# ADDER_auto.net
KiCad netlist of a schematic drawn in EAGLE
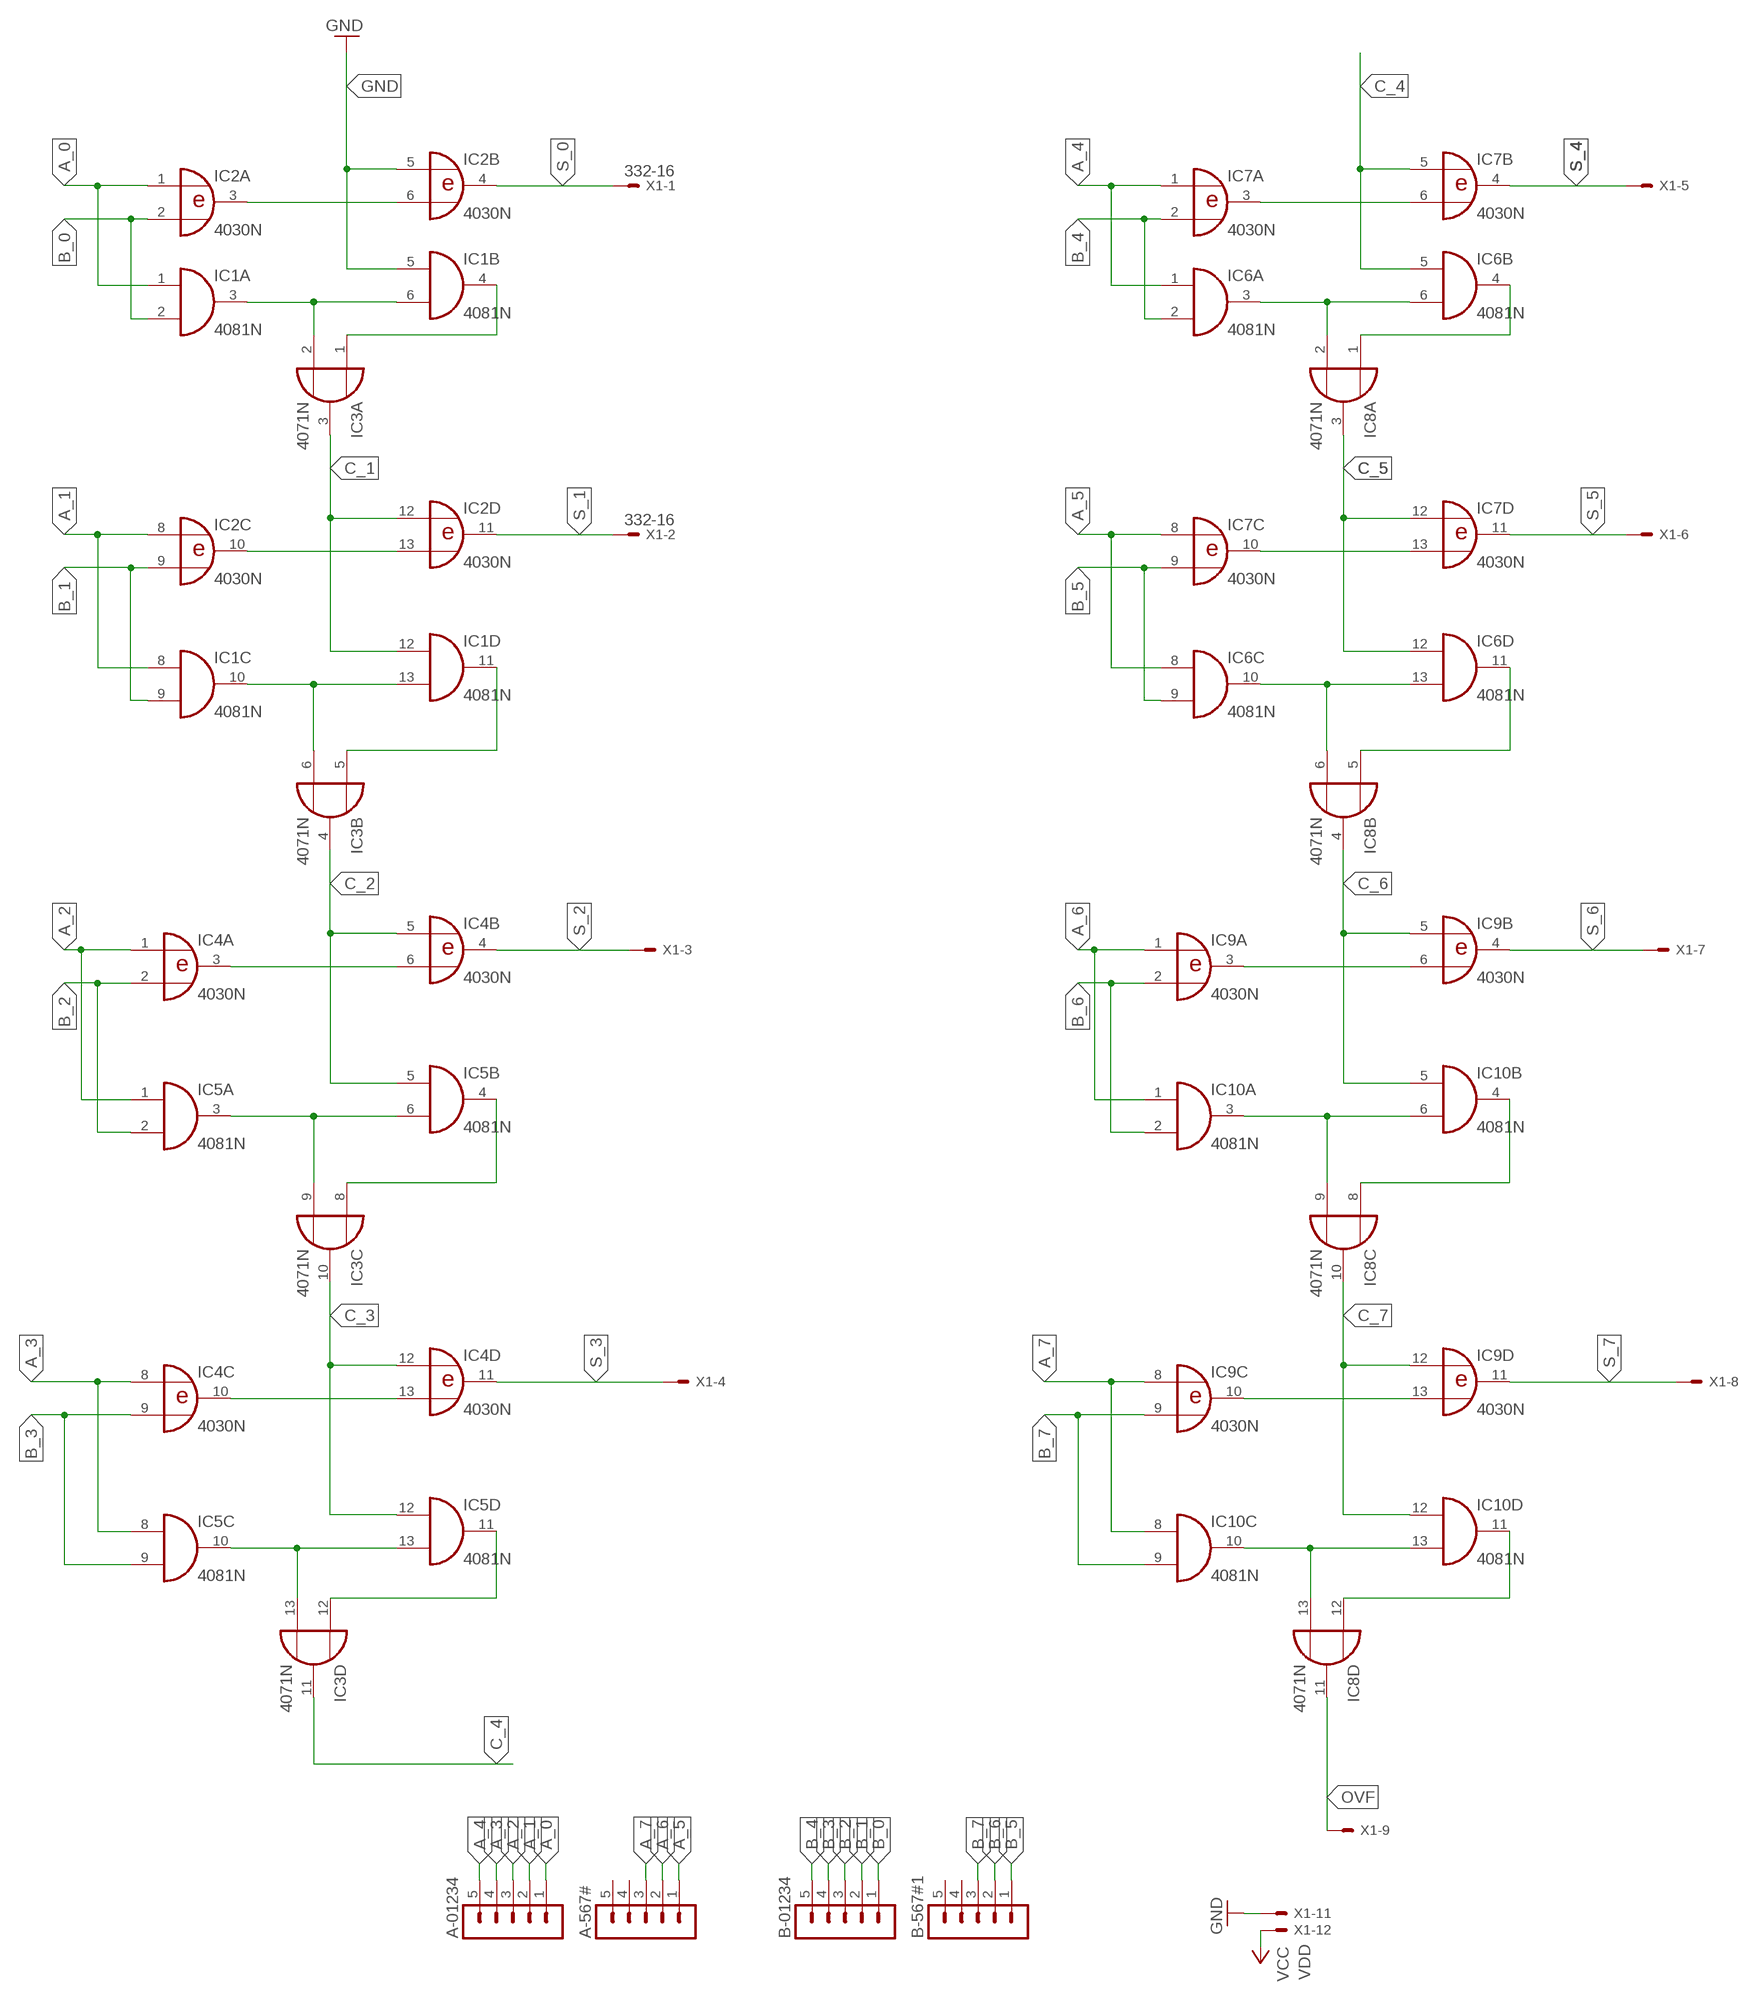
[diagram p0: schematic, sheet 1]

(export (version "E")
  (design (tool "Eeschema 10.0.6"))
  (components
    (comp (ref "A-567#")
      (value "MA05-1")
      (footprint "eagle-import:MA05-1")
      (libsource (lib "eagle-import") (part "MA05-1"))
    )
    (comp (ref "A-01234")
      (value "MA05-1")
      (footprint "eagle-import:MA05-1")
      (libsource (lib "eagle-import") (part "MA05-1"))
    )
    (comp (ref "B-567#1")
      (value "MA05-1")
      (footprint "eagle-import:MA05-1")
      (libsource (lib "eagle-import") (part "MA05-1"))
    )
    (comp (ref "B-01234")
      (value "MA05-1")
      (footprint "eagle-import:MA05-1")
      (libsource (lib "eagle-import") (part "MA05-1"))
    )
    (comp (ref "IC1")
      (value "4081N")
      (footprint "eagle-import:DIL14")
      (libsource (lib "eagle-import") (part "4081N"))
    )
    (comp (ref "IC2")
      (value "4030N")
      (footprint "eagle-import:DIL14")
      (libsource (lib "eagle-import") (part "4030N"))
    )
    (comp (ref "IC3")
      (value "4071N")
      (footprint "eagle-import:DIL14")
      (libsource (lib "eagle-import") (part "4071N"))
    )
    (comp (ref "IC4")
      (value "4030N")
      (footprint "eagle-import:DIL14")
      (libsource (lib "eagle-import") (part "4030N"))
    )
    (comp (ref "IC5")
      (value "4081N")
      (footprint "eagle-import:DIL14")
      (libsource (lib "eagle-import") (part "4081N"))
    )
    (comp (ref "IC6")
      (value "4081N")
      (footprint "eagle-import:DIL14")
      (libsource (lib "eagle-import") (part "4081N"))
    )
    (comp (ref "IC7")
      (value "4030N")
      (footprint "eagle-import:DIL14")
      (libsource (lib "eagle-import") (part "4030N"))
    )
    (comp (ref "IC8")
      (value "4071N")
      (footprint "eagle-import:DIL14")
      (libsource (lib "eagle-import") (part "4071N"))
    )
    (comp (ref "IC9")
      (value "4030N")
      (footprint "eagle-import:DIL14")
      (libsource (lib "eagle-import") (part "4030N"))
    )
    (comp (ref "IC10")
      (value "4081N")
      (footprint "eagle-import:DIL14")
      (libsource (lib "eagle-import") (part "4081N"))
    )
    (comp (ref "X1")
      (value "332-16")
      (footprint "eagle-import:332-16")
      (libsource (lib "eagle-import") (part "332-16"))
    )
  )
  (nets
    (net (code "1") (name "A_0") (class "Default")
      (node (ref "A-01234") (pin "1") (pinfunction "1_1") (pintype "passive"))
      (node (ref "IC1") (pin "1") (pinfunction "I0_1") (pintype "input"))
      (node (ref "IC2") (pin "1") (pinfunction "I0_1") (pintype "input"))
    )
    (net (code "2") (name "A_1") (class "Default")
      (node (ref "A-01234") (pin "2") (pinfunction "2_2") (pintype "passive"))
      (node (ref "IC1") (pin "8") (pinfunction "I0_8") (pintype "input"))
      (node (ref "IC2") (pin "8") (pinfunction "I0_8") (pintype "input"))
    )
    (net (code "3") (name "A_2") (class "Default")
      (node (ref "A-01234") (pin "3") (pinfunction "3_3") (pintype "passive"))
      (node (ref "IC4") (pin "1") (pinfunction "I0_1") (pintype "input"))
      (node (ref "IC5") (pin "1") (pinfunction "I0_1") (pintype "input"))
    )
    (net (code "4") (name "A_3") (class "Default")
      (node (ref "A-01234") (pin "4") (pinfunction "4_4") (pintype "passive"))
      (node (ref "IC4") (pin "8") (pinfunction "I0_8") (pintype "input"))
      (node (ref "IC5") (pin "8") (pinfunction "I0_8") (pintype "input"))
    )
    (net (code "5") (name "A_4") (class "Default")
      (node (ref "A-01234") (pin "5") (pinfunction "5_5") (pintype "passive"))
      (node (ref "IC6") (pin "1") (pinfunction "I0_1") (pintype "input"))
      (node (ref "IC7") (pin "1") (pinfunction "I0_1") (pintype "input"))
    )
    (net (code "6") (name "A_5") (class "Default")
      (node (ref "A-567#") (pin "1") (pinfunction "1_1") (pintype "passive"))
      (node (ref "IC6") (pin "8") (pinfunction "I0_8") (pintype "input"))
      (node (ref "IC7") (pin "8") (pinfunction "I0_8") (pintype "input"))
    )
    (net (code "7") (name "A_6") (class "Default")
      (node (ref "A-567#") (pin "2") (pinfunction "2_2") (pintype "passive"))
      (node (ref "IC10") (pin "1") (pinfunction "I0_1") (pintype "input"))
      (node (ref "IC9") (pin "1") (pinfunction "I0_1") (pintype "input"))
    )
    (net (code "8") (name "A_7") (class "Default")
      (node (ref "A-567#") (pin "3") (pinfunction "3_3") (pintype "passive"))
      (node (ref "IC10") (pin "8") (pinfunction "I0_8") (pintype "input"))
      (node (ref "IC9") (pin "8") (pinfunction "I0_8") (pintype "input"))
    )
    (net (code "9") (name "B_0") (class "Default")
      (node (ref "B-01234") (pin "1") (pinfunction "1_1") (pintype "passive"))
      (node (ref "IC1") (pin "2") (pinfunction "I1_2") (pintype "input"))
      (node (ref "IC2") (pin "2") (pinfunction "I1_2") (pintype "input"))
    )
    (net (code "10") (name "B_1") (class "Default")
      (node (ref "B-01234") (pin "2") (pinfunction "2_2") (pintype "passive"))
      (node (ref "IC1") (pin "9") (pinfunction "I1_9") (pintype "input"))
      (node (ref "IC2") (pin "9") (pinfunction "I1_9") (pintype "input"))
    )
    (net (code "11") (name "B_2") (class "Default")
      (node (ref "B-01234") (pin "3") (pinfunction "3_3") (pintype "passive"))
      (node (ref "IC4") (pin "2") (pinfunction "I1_2") (pintype "input"))
      (node (ref "IC5") (pin "2") (pinfunction "I1_2") (pintype "input"))
    )
    (net (code "12") (name "B_3") (class "Default")
      (node (ref "B-01234") (pin "4") (pinfunction "4_4") (pintype "passive"))
      (node (ref "IC4") (pin "9") (pinfunction "I1_9") (pintype "input"))
      (node (ref "IC5") (pin "9") (pinfunction "I1_9") (pintype "input"))
    )
    (net (code "13") (name "B_4") (class "Default")
      (node (ref "B-01234") (pin "5") (pinfunction "5_5") (pintype "passive"))
      (node (ref "IC6") (pin "2") (pinfunction "I1_2") (pintype "input"))
      (node (ref "IC7") (pin "2") (pinfunction "I1_2") (pintype "input"))
    )
    (net (code "14") (name "B_5") (class "Default")
      (node (ref "B-567#1") (pin "1") (pinfunction "1_1") (pintype "passive"))
      (node (ref "IC6") (pin "9") (pinfunction "I1_9") (pintype "input"))
      (node (ref "IC7") (pin "9") (pinfunction "I1_9") (pintype "input"))
    )
    (net (code "15") (name "B_6") (class "Default")
      (node (ref "B-567#1") (pin "2") (pinfunction "2_2") (pintype "passive"))
      (node (ref "IC10") (pin "2") (pinfunction "I1_2") (pintype "input"))
      (node (ref "IC9") (pin "2") (pinfunction "I1_2") (pintype "input"))
    )
    (net (code "16") (name "B_7") (class "Default")
      (node (ref "B-567#1") (pin "3") (pinfunction "3_3") (pintype "passive"))
      (node (ref "IC10") (pin "9") (pinfunction "I1_9") (pintype "input"))
      (node (ref "IC9") (pin "9") (pinfunction "I1_9") (pintype "input"))
    )
    (net (code "17") (name "C_1") (class "Default")
      (node (ref "IC1") (pin "12") (pinfunction "I0_12") (pintype "input"))
      (node (ref "IC2") (pin "12") (pinfunction "I0_12") (pintype "input"))
      (node (ref "IC3") (pin "3") (pinfunction "O_3") (pintype "output"))
    )
    (net (code "18") (name "C_2") (class "Default")
      (node (ref "IC3") (pin "4") (pinfunction "O_4") (pintype "output"))
      (node (ref "IC4") (pin "5") (pinfunction "I0_5") (pintype "input"))
      (node (ref "IC5") (pin "5") (pinfunction "I0_5") (pintype "input"))
    )
    (net (code "19") (name "C_3") (class "Default")
      (node (ref "IC3") (pin "10") (pinfunction "O_10") (pintype "output"))
      (node (ref "IC4") (pin "12") (pinfunction "I0_12") (pintype "input"))
      (node (ref "IC5") (pin "12") (pinfunction "I0_12") (pintype "input"))
    )
    (net (code "20") (name "C_4") (class "Default")
      (node (ref "IC3") (pin "11") (pinfunction "O_11") (pintype "output"))
      (node (ref "IC6") (pin "5") (pinfunction "I0_5") (pintype "input"))
      (node (ref "IC7") (pin "5") (pinfunction "I0_5") (pintype "input"))
    )
    (net (code "21") (name "C_5") (class "Default")
      (node (ref "IC6") (pin "12") (pinfunction "I0_12") (pintype "input"))
      (node (ref "IC7") (pin "12") (pinfunction "I0_12") (pintype "input"))
      (node (ref "IC8") (pin "3") (pinfunction "O_3") (pintype "output"))
    )
    (net (code "22") (name "C_6") (class "Default")
      (node (ref "IC10") (pin "5") (pinfunction "I0_5") (pintype "input"))
      (node (ref "IC8") (pin "4") (pinfunction "O_4") (pintype "output"))
      (node (ref "IC9") (pin "5") (pinfunction "I0_5") (pintype "input"))
    )
    (net (code "23") (name "C_7") (class "Default")
      (node (ref "IC10") (pin "12") (pinfunction "I0_12") (pintype "input"))
      (node (ref "IC8") (pin "10") (pinfunction "O_10") (pintype "output"))
      (node (ref "IC9") (pin "12") (pinfunction "I0_12") (pintype "input"))
    )
    (net (code "24") (name "GND") (class "Default")
      (node (ref "IC1") (pin "5") (pinfunction "I0_5") (pintype "input"))
      (node (ref "IC2") (pin "5") (pinfunction "I0_5") (pintype "input"))
      (node (ref "X1") (pin "11") (pinfunction "S_11") (pintype "passive"))
    )
    (net (code "25") (name "Net-(IC1A-O)") (class "Default")
      (node (ref "IC1") (pin "3") (pinfunction "O_3") (pintype "output"))
      (node (ref "IC1") (pin "6") (pinfunction "I1_6") (pintype "input"))
      (node (ref "IC3") (pin "2") (pinfunction "I1_2") (pintype "input"))
    )
    (net (code "26") (name "Net-(IC1B-O)") (class "Default")
      (node (ref "IC1") (pin "4") (pinfunction "O_4") (pintype "output"))
      (node (ref "IC3") (pin "1") (pinfunction "I0_1") (pintype "input"))
    )
    (net (code "27") (name "Net-(IC1C-O)") (class "Default")
      (node (ref "IC1") (pin "10") (pinfunction "O_10") (pintype "output"))
      (node (ref "IC1") (pin "13") (pinfunction "I1_13") (pintype "input"))
      (node (ref "IC3") (pin "6") (pinfunction "I1_6") (pintype "input"))
    )
    (net (code "28") (name "Net-(IC1D-O)") (class "Default")
      (node (ref "IC1") (pin "11") (pinfunction "O_11") (pintype "output"))
      (node (ref "IC3") (pin "5") (pinfunction "I0_5") (pintype "input"))
    )
    (net (code "29") (name "Net-(IC2A-O)") (class "Default")
      (node (ref "IC2") (pin "3") (pinfunction "O_3") (pintype "output"))
      (node (ref "IC2") (pin "6") (pinfunction "I1_6") (pintype "input"))
    )
    (net (code "30") (name "Net-(IC2C-O)") (class "Default")
      (node (ref "IC2") (pin "10") (pinfunction "O_10") (pintype "output"))
      (node (ref "IC2") (pin "13") (pinfunction "I1_13") (pintype "input"))
    )
    (net (code "31") (name "Net-(IC3C-I0)") (class "Default")
      (node (ref "IC3") (pin "8") (pinfunction "I0_8") (pintype "input"))
      (node (ref "IC5") (pin "4") (pinfunction "O_4") (pintype "output"))
    )
    (net (code "32") (name "Net-(IC3C-I1)") (class "Default")
      (node (ref "IC3") (pin "9") (pinfunction "I1_9") (pintype "input"))
      (node (ref "IC5") (pin "3") (pinfunction "O_3") (pintype "output"))
      (node (ref "IC5") (pin "6") (pinfunction "I1_6") (pintype "input"))
    )
    (net (code "33") (name "Net-(IC3D-I0)") (class "Default")
      (node (ref "IC3") (pin "12") (pinfunction "I0_12") (pintype "input"))
      (node (ref "IC5") (pin "11") (pinfunction "O_11") (pintype "output"))
    )
    (net (code "34") (name "Net-(IC3D-I1)") (class "Default")
      (node (ref "IC3") (pin "13") (pinfunction "I1_13") (pintype "input"))
      (node (ref "IC5") (pin "10") (pinfunction "O_10") (pintype "output"))
      (node (ref "IC5") (pin "13") (pinfunction "I1_13") (pintype "input"))
    )
    (net (code "35") (name "Net-(IC4A-O)") (class "Default")
      (node (ref "IC4") (pin "3") (pinfunction "O_3") (pintype "output"))
      (node (ref "IC4") (pin "6") (pinfunction "I1_6") (pintype "input"))
    )
    (net (code "36") (name "Net-(IC4C-O)") (class "Default")
      (node (ref "IC4") (pin "10") (pinfunction "O_10") (pintype "output"))
      (node (ref "IC4") (pin "13") (pinfunction "I1_13") (pintype "input"))
    )
    (net (code "37") (name "Net-(IC6A-O)") (class "Default")
      (node (ref "IC6") (pin "3") (pinfunction "O_3") (pintype "output"))
      (node (ref "IC6") (pin "6") (pinfunction "I1_6") (pintype "input"))
      (node (ref "IC8") (pin "2") (pinfunction "I1_2") (pintype "input"))
    )
    (net (code "38") (name "Net-(IC6B-O)") (class "Default")
      (node (ref "IC6") (pin "4") (pinfunction "O_4") (pintype "output"))
      (node (ref "IC8") (pin "1") (pinfunction "I0_1") (pintype "input"))
    )
    (net (code "39") (name "Net-(IC6C-O)") (class "Default")
      (node (ref "IC6") (pin "10") (pinfunction "O_10") (pintype "output"))
      (node (ref "IC6") (pin "13") (pinfunction "I1_13") (pintype "input"))
      (node (ref "IC8") (pin "6") (pinfunction "I1_6") (pintype "input"))
    )
    (net (code "40") (name "Net-(IC6D-O)") (class "Default")
      (node (ref "IC6") (pin "11") (pinfunction "O_11") (pintype "output"))
      (node (ref "IC8") (pin "5") (pinfunction "I0_5") (pintype "input"))
    )
    (net (code "41") (name "Net-(IC7A-O)") (class "Default")
      (node (ref "IC7") (pin "3") (pinfunction "O_3") (pintype "output"))
      (node (ref "IC7") (pin "6") (pinfunction "I1_6") (pintype "input"))
    )
    (net (code "42") (name "Net-(IC7C-O)") (class "Default")
      (node (ref "IC7") (pin "10") (pinfunction "O_10") (pintype "output"))
      (node (ref "IC7") (pin "13") (pinfunction "I1_13") (pintype "input"))
    )
    (net (code "43") (name "Net-(IC9A-O)") (class "Default")
      (node (ref "IC9") (pin "3") (pinfunction "O_3") (pintype "output"))
      (node (ref "IC9") (pin "6") (pinfunction "I1_6") (pintype "input"))
    )
    (net (code "44") (name "Net-(IC9C-O)") (class "Default")
      (node (ref "IC9") (pin "10") (pinfunction "O_10") (pintype "output"))
      (node (ref "IC9") (pin "13") (pinfunction "I1_13") (pintype "input"))
    )
    (net (code "45") (name "Net-(IC10A-O)") (class "Default")
      (node (ref "IC10") (pin "3") (pinfunction "O_3") (pintype "output"))
      (node (ref "IC10") (pin "6") (pinfunction "I1_6") (pintype "input"))
      (node (ref "IC8") (pin "9") (pinfunction "I1_9") (pintype "input"))
    )
    (net (code "46") (name "Net-(IC10B-O)") (class "Default")
      (node (ref "IC10") (pin "4") (pinfunction "O_4") (pintype "output"))
      (node (ref "IC8") (pin "8") (pinfunction "I0_8") (pintype "input"))
    )
    (net (code "47") (name "Net-(IC10C-O)") (class "Default")
      (node (ref "IC10") (pin "10") (pinfunction "O_10") (pintype "output"))
      (node (ref "IC10") (pin "13") (pinfunction "I1_13") (pintype "input"))
      (node (ref "IC8") (pin "13") (pinfunction "I1_13") (pintype "input"))
    )
    (net (code "48") (name "Net-(IC10D-O)") (class "Default")
      (node (ref "IC10") (pin "11") (pinfunction "O_11") (pintype "output"))
      (node (ref "IC8") (pin "12") (pinfunction "I0_12") (pintype "input"))
    )
    (net (code "49") (name "OVF") (class "Default")
      (node (ref "IC8") (pin "11") (pinfunction "O_11") (pintype "output"))
      (node (ref "X1") (pin "9") (pinfunction "S_9") (pintype "passive"))
    )
    (net (code "50") (name "S_0") (class "Default")
      (node (ref "IC2") (pin "4") (pinfunction "O_4") (pintype "output"))
      (node (ref "X1") (pin "1") (pinfunction "S_1") (pintype "passive"))
    )
    (net (code "51") (name "S_1") (class "Default")
      (node (ref "IC2") (pin "11") (pinfunction "O_11") (pintype "output"))
      (node (ref "X1") (pin "2") (pinfunction "S_2") (pintype "passive"))
    )
    (net (code "52") (name "S_2") (class "Default")
      (node (ref "IC4") (pin "4") (pinfunction "O_4") (pintype "output"))
      (node (ref "X1") (pin "3") (pinfunction "S_3") (pintype "passive"))
    )
    (net (code "53") (name "S_3") (class "Default")
      (node (ref "IC4") (pin "11") (pinfunction "O_11") (pintype "output"))
      (node (ref "X1") (pin "4") (pinfunction "S_4") (pintype "passive"))
    )
    (net (code "54") (name "S_4") (class "Default")
      (node (ref "IC7") (pin "4") (pinfunction "O_4") (pintype "output"))
      (node (ref "X1") (pin "5") (pinfunction "S_5") (pintype "passive"))
    )
    (net (code "55") (name "S_5") (class "Default")
      (node (ref "IC7") (pin "11") (pinfunction "O_11") (pintype "output"))
      (node (ref "X1") (pin "6") (pinfunction "S_6") (pintype "passive"))
    )
    (net (code "56") (name "S_6") (class "Default")
      (node (ref "IC9") (pin "4") (pinfunction "O_4") (pintype "output"))
      (node (ref "X1") (pin "7") (pinfunction "S_7") (pintype "passive"))
    )
    (net (code "57") (name "S_7") (class "Default")
      (node (ref "IC9") (pin "11") (pinfunction "O_11") (pintype "output"))
      (node (ref "X1") (pin "8") (pinfunction "S_8") (pintype "passive"))
    )
    (net (code "58") (name "VCC") (class "Default")
      (node (ref "X1") (pin "12") (pinfunction "S_12") (pintype "passive"))
    )
    (net (code "59") (name "unconnected-(A-567#-Pad4)") (class "Default")
      (node (ref "A-567#") (pin "4") (pinfunction "4_4") (pintype "passive"))
    )
    (net (code "60") (name "unconnected-(A-567#-Pad5)") (class "Default")
      (node (ref "A-567#") (pin "5") (pinfunction "5_5") (pintype "passive"))
    )
    (net (code "61") (name "unconnected-(B-567#1-Pad4)") (class "Default")
      (node (ref "B-567#1") (pin "4") (pinfunction "4_4") (pintype "passive"))
    )
    (net (code "62") (name "unconnected-(B-567#1-Pad5)") (class "Default")
      (node (ref "B-567#1") (pin "5") (pinfunction "5_5") (pintype "passive"))
    )
  )
)
